# mpc56_can.net
KiCad netlist of a schematic drawn in Altium Designer
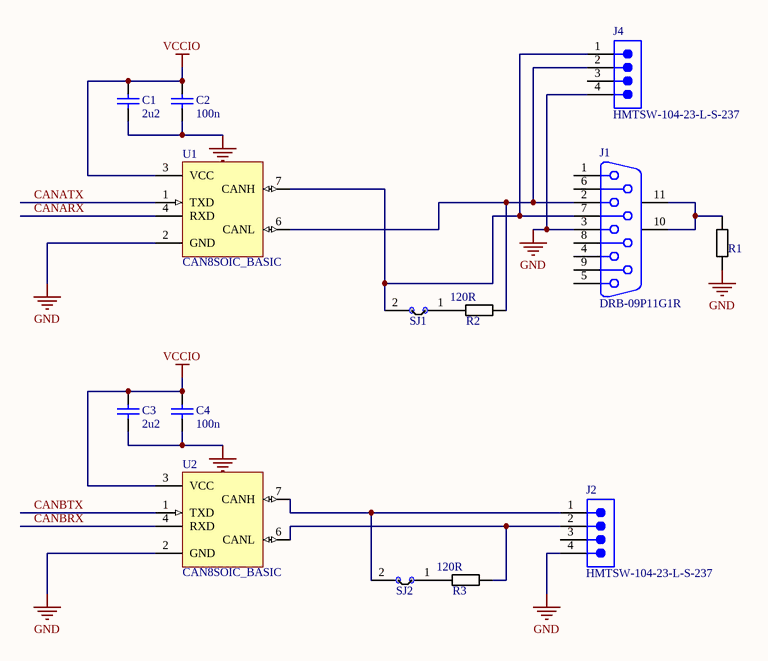
[diagram p0: mpc56_can.SchDoc]

(export (version "E")
  (design (tool "Eeschema 10.0.6"))
  (components
    (comp (ref "C1")
      (value "2u2")
      (footprint "CAPC0603_M")
      (description "2u2, 0603")
      (fields (field (name "PART NUMBER") "CCHIP-2u2-0603"))
      (libsource (lib "NewAE_AltiumLib") (part "CAP"))
    )
    (comp (ref "C2")
      (value "100n")
      (footprint "CAPC0402_M")
      (description "100n, 0402")
      (fields (field (name "PART NUMBER") "CCHIP-100n-0402"))
      (libsource (lib "NewAE_AltiumLib") (part "CAP"))
    )
    (comp (ref "C3")
      (value "2u2")
      (footprint "CAPC0603_M")
      (description "2u2, 0603")
      (fields (field (name "PART NUMBER") "CCHIP-2u2-0603"))
      (libsource (lib "NewAE_AltiumLib") (part "CAP"))
    )
    (comp (ref "C4")
      (value "100n")
      (footprint "CAPC0402_M")
      (description "100n, 0402")
      (fields (field (name "PART NUMBER") "CCHIP-100n-0402"))
      (libsource (lib "NewAE_AltiumLib") (part "CAP"))
    )
    (comp (ref "J1")
      (value "DRB-09P11G1R")
      (footprint "TAIT-DRB-09P11G1R_V")
      (description "DB9 R/A Connector, Through-hole, Male")
      (libsource (lib "Altium Content Vault") (part "TAIT-DRB-09P11G1R-9"))
    )
    (comp (ref "J2")
      (value "HMTSW-104-23-L-S-237")
      (footprint "SMTC-HMTSW-104-23-X-S-237")
      (fields (field (name "MANUFACTURER") "Samtec"))
      (libsource (lib "Altium Content Vault") (part "CMP-1024-00020-1"))
    )
    (comp (ref "J4")
      (value "HMTSW-104-23-L-S-237")
      (footprint "SMTC-HMTSW-104-23-X-S-237")
      (fields (field (name "MANUFACTURER") "Samtec"))
      (libsource (lib "Altium Content Vault") (part "CMP-1024-00020-1"))
    )
    (comp (ref "R1")
      (value "10R")
      (footprint "RESC1608X55N")
      (description "10R res, 0603, 1%, 1/10W")
      (fields (field (name "PART NUMBER") "RCHIP-10R-0603") (field (name "TOLERANCE") "1%"))
      (libsource (lib "NewAE_AltiumLib") (part "RES-EU"))
    )
    (comp (ref "R2")
      (value "120R")
      (footprint "RESC1608X55N")
      (description "120R res, 0603, 1%, 1/10W")
      (fields (field (name "PART NUMBER") "RCHIP-120R-0603") (field (name "TOLERANCE") "1%"))
      (libsource (lib "") (part "RES-EU_1"))
    )
    (comp (ref "R3")
      (value "120R")
      (footprint "RESC1608X55N")
      (description "120R res, 0603, 1%, 1/10W")
      (fields (field (name "PART NUMBER") "RCHIP-120R-0603") (field (name "TOLERANCE") "1%"))
      (libsource (lib "") (part "RES-EU_1"))
    )
    (comp (ref "SJ1")
      (value "NC")
      (footprint "SJ_2S_NC")
      (description "Solder Jumper, NC")
      (fields (field (name "PART NUMBER") "SJ_2S"))
      (libsource (lib "NewAE_AltiumLib") (part "SJ_2S"))
    )
    (comp (ref "SJ2")
      (value "NC")
      (footprint "SJ_2S_NC")
      (description "Solder Jumper, NC")
      (fields (field (name "PART NUMBER") "SJ_2S"))
      (libsource (lib "NewAE_AltiumLib") (part "SJ_2S"))
    )
    (comp (ref "U1")
      (value "CAN8SOIC_BASIC")
      (footprint "SOIC8_NARROW")
      (description "CAN Transceiver, 3.3V")
      (fields (field (name "PART NUMBER") "SN65HVD232DR"))
      (libsource (lib "NewAE_AltiumLib") (part "CAN8SOIC_BASIC"))
    )
    (comp (ref "U2")
      (value "CAN8SOIC_BASIC")
      (footprint "SOIC8_NARROW")
      (description "CAN Transceiver, 3.3V")
      (fields (field (name "PART NUMBER") "SN65HVD232DR"))
      (libsource (lib "NewAE_AltiumLib") (part "CAN8SOIC_BASIC"))
    )
  )
  (nets
    (net (code "1") (name "/CANARX") (class "Default")
      (node (ref "U1") (pin "4") (pinfunction "RXD_4") (pintype "tri_state"))
    )
    (net (code "2") (name "/CANATX") (class "Default")
      (node (ref "U1") (pin "1") (pinfunction "TXD_1") (pintype "input"))
    )
    (net (code "3") (name "/CANBRX") (class "Default")
      (node (ref "U2") (pin "4") (pinfunction "RXD_4") (pintype "tri_state"))
    )
    (net (code "4") (name "/CANBTX") (class "Default")
      (node (ref "U2") (pin "1") (pinfunction "TXD_1") (pintype "input"))
    )
    (net (code "5") (name "GND") (class "Default")
      (node (ref "C1") (pin "2") (pinfunction "2_2") (pintype "passive"))
      (node (ref "C2") (pin "2") (pinfunction "2_2") (pintype "passive"))
      (node (ref "C3") (pin "2") (pinfunction "2_2") (pintype "passive"))
      (node (ref "C4") (pin "2") (pinfunction "2_2") (pintype "passive"))
      (node (ref "J1") (pin "3") (pinfunction "3_3") (pintype "passive"))
      (node (ref "J2") (pin "4") (pinfunction "4_4") (pintype "passive"))
      (node (ref "J4") (pin "4") (pinfunction "4_4") (pintype "passive"))
      (node (ref "R1") (pin "1") (pinfunction "1_1") (pintype "passive"))
      (node (ref "U1") (pin "2") (pinfunction "GND_2") (pintype "power_in"))
      (node (ref "U2") (pin "2") (pinfunction "GND_2") (pintype "power_in"))
    )
    (net (code "6") (name "Net-(J1-MH1)") (class "Default")
      (node (ref "J1") (pin "10") (pinfunction "MH1_10") (pintype "passive"))
      (node (ref "J1") (pin "11") (pinfunction "MH2_11") (pintype "passive"))
      (node (ref "R1") (pin "2") (pinfunction "2_2") (pintype "passive"))
    )
    (net (code "7") (name "Net-(R2-Pad1)") (class "Default")
      (node (ref "R2") (pin "1") (pinfunction "1_1") (pintype "passive"))
      (node (ref "SJ1") (pin "1") (pinfunction "1_1") (pintype "passive"))
    )
    (net (code "8") (name "Net-(R3-Pad1)") (class "Default")
      (node (ref "R3") (pin "1") (pinfunction "1_1") (pintype "passive"))
      (node (ref "SJ2") (pin "1") (pinfunction "1_1") (pintype "passive"))
    )
    (net (code "9") (name "Net-(U1-CANH)") (class "Default")
      (node (ref "J1") (pin "7") (pinfunction "7_7") (pintype "passive"))
      (node (ref "J4") (pin "1") (pinfunction "1_1") (pintype "passive"))
      (node (ref "SJ1") (pin "2") (pinfunction "2_2") (pintype "passive"))
      (node (ref "U1") (pin "7") (pinfunction "CANH_7") (pintype "bidirectional"))
    )
    (net (code "10") (name "Net-(U1-CANL)") (class "Default")
      (node (ref "J1") (pin "2") (pinfunction "2_2") (pintype "passive"))
      (node (ref "J4") (pin "2") (pinfunction "2_2") (pintype "passive"))
      (node (ref "R2") (pin "2") (pinfunction "2_2") (pintype "passive"))
      (node (ref "U1") (pin "6") (pinfunction "CANL_6") (pintype "bidirectional"))
    )
    (net (code "11") (name "Net-(U2-CANH)") (class "Default")
      (node (ref "J2") (pin "1") (pinfunction "1_1") (pintype "passive"))
      (node (ref "SJ2") (pin "2") (pinfunction "2_2") (pintype "passive"))
      (node (ref "U2") (pin "7") (pinfunction "CANH_7") (pintype "bidirectional"))
    )
    (net (code "12") (name "Net-(U2-CANL)") (class "Default")
      (node (ref "J2") (pin "2") (pinfunction "2_2") (pintype "passive"))
      (node (ref "R3") (pin "2") (pinfunction "2_2") (pintype "passive"))
      (node (ref "U2") (pin "6") (pinfunction "CANL_6") (pintype "bidirectional"))
    )
    (net (code "13") (name "VCCIO") (class "Default")
      (node (ref "C1") (pin "1") (pinfunction "1_1") (pintype "passive"))
      (node (ref "C2") (pin "1") (pinfunction "1_1") (pintype "passive"))
      (node (ref "C3") (pin "1") (pinfunction "1_1") (pintype "passive"))
      (node (ref "C4") (pin "1") (pinfunction "1_1") (pintype "passive"))
      (node (ref "U1") (pin "3") (pinfunction "VCC_3") (pintype "power_in"))
      (node (ref "U2") (pin "3") (pinfunction "VCC_3") (pintype "power_in"))
    )
    (net (code "14") (name "unconnected-(J1-Pad1)") (class "Default")
      (node (ref "J1") (pin "1") (pinfunction "1_1") (pintype "passive"))
    )
    (net (code "15") (name "unconnected-(J1-Pad4)") (class "Default")
      (node (ref "J1") (pin "4") (pinfunction "4_4") (pintype "passive"))
    )
    (net (code "16") (name "unconnected-(J1-Pad5)") (class "Default")
      (node (ref "J1") (pin "5") (pinfunction "5_5") (pintype "passive"))
    )
    (net (code "17") (name "unconnected-(J1-Pad6)") (class "Default")
      (node (ref "J1") (pin "6") (pinfunction "6_6") (pintype "passive"))
    )
    (net (code "18") (name "unconnected-(J1-Pad8)") (class "Default")
      (node (ref "J1") (pin "8") (pinfunction "8_8") (pintype "passive"))
    )
    (net (code "19") (name "unconnected-(J1-Pad9)") (class "Default")
      (node (ref "J1") (pin "9") (pinfunction "9_9") (pintype "passive"))
    )
    (net (code "20") (name "unconnected-(J2-Pad3)") (class "Default")
      (node (ref "J2") (pin "3") (pinfunction "3_3") (pintype "passive"))
    )
    (net (code "21") (name "unconnected-(J4-Pad3)") (class "Default")
      (node (ref "J4") (pin "3") (pinfunction "3_3") (pintype "passive"))
    )
  )
)
